# IR-comms-out.net
KiCad netlist of a schematic drawn in EAGLE
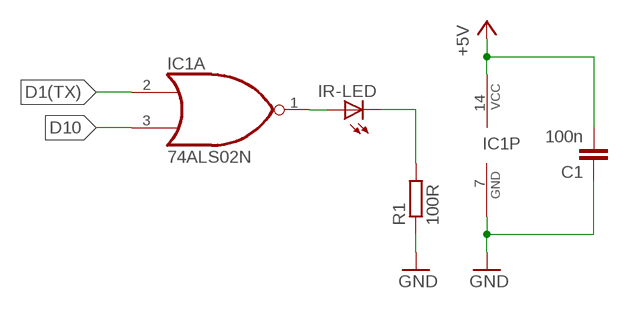
[diagram p0: schematic, sheet 1]

(export (version "E")
  (design (tool "Eeschema 10.0.6"))
  (components
    (comp (ref "C1")
      (value "100n")
      (footprint "eagle-import:C025-024X044")
      (libsource (lib "eagle-import") (part "C-EU025-024X044"))
    )
    (comp (ref "IC1")
      (value "74ALS02N")
      (footprint "eagle-import:DIL14")
      (libsource (lib "eagle-import") (part "7402NALS"))
    )
    (comp (ref "IR-LED")
      (value "LED5MM")
      (footprint "eagle-import:LED5MM")
      (libsource (lib "eagle-import") (part "LED5MM"))
    )
    (comp (ref "R1")
      (value "100R")
      (footprint "eagle-import:0204V")
      (libsource (lib "eagle-import") (part "R-EU_0204/2V"))
    )
  )
  (nets
    (net (code "1") (name "+5V") (class "Default")
      (node (ref "C1") (pin "2") (pinfunction "2_2") (pintype "passive"))
      (node (ref "IC1") (pin "14") (pinfunction "VCC_14") (pintype "power_in"))
    )
    (net (code "2") (name "D1(TX)") (class "Default")
      (node (ref "IC1") (pin "2") (pinfunction "I0_2") (pintype "input"))
    )
    (net (code "3") (name "D10") (class "Default")
      (node (ref "IC1") (pin "3") (pinfunction "I1_3") (pintype "input"))
    )
    (net (code "4") (name "GND") (class "Default")
      (node (ref "C1") (pin "1") (pinfunction "1_1") (pintype "passive"))
      (node (ref "IC1") (pin "7") (pinfunction "GND_7") (pintype "power_in"))
      (node (ref "R1") (pin "1") (pinfunction "1_1") (pintype "passive"))
    )
    (net (code "5") (name "Net-(IC1A-O)") (class "Default")
      (node (ref "IC1") (pin "1") (pinfunction "O_1") (pintype "output"))
      (node (ref "IR-LED") (pin "A") (pinfunction "A_A") (pintype "passive"))
    )
    (net (code "6") (name "Net-(IR-LED-C)") (class "Default")
      (node (ref "IR-LED") (pin "K") (pinfunction "C_K") (pintype "passive"))
      (node (ref "R1") (pin "2") (pinfunction "2_2") (pintype "passive"))
    )
  )
)
